# LEFT_CCM.net
KiCad netlist of a schematic drawn in Altium Designer
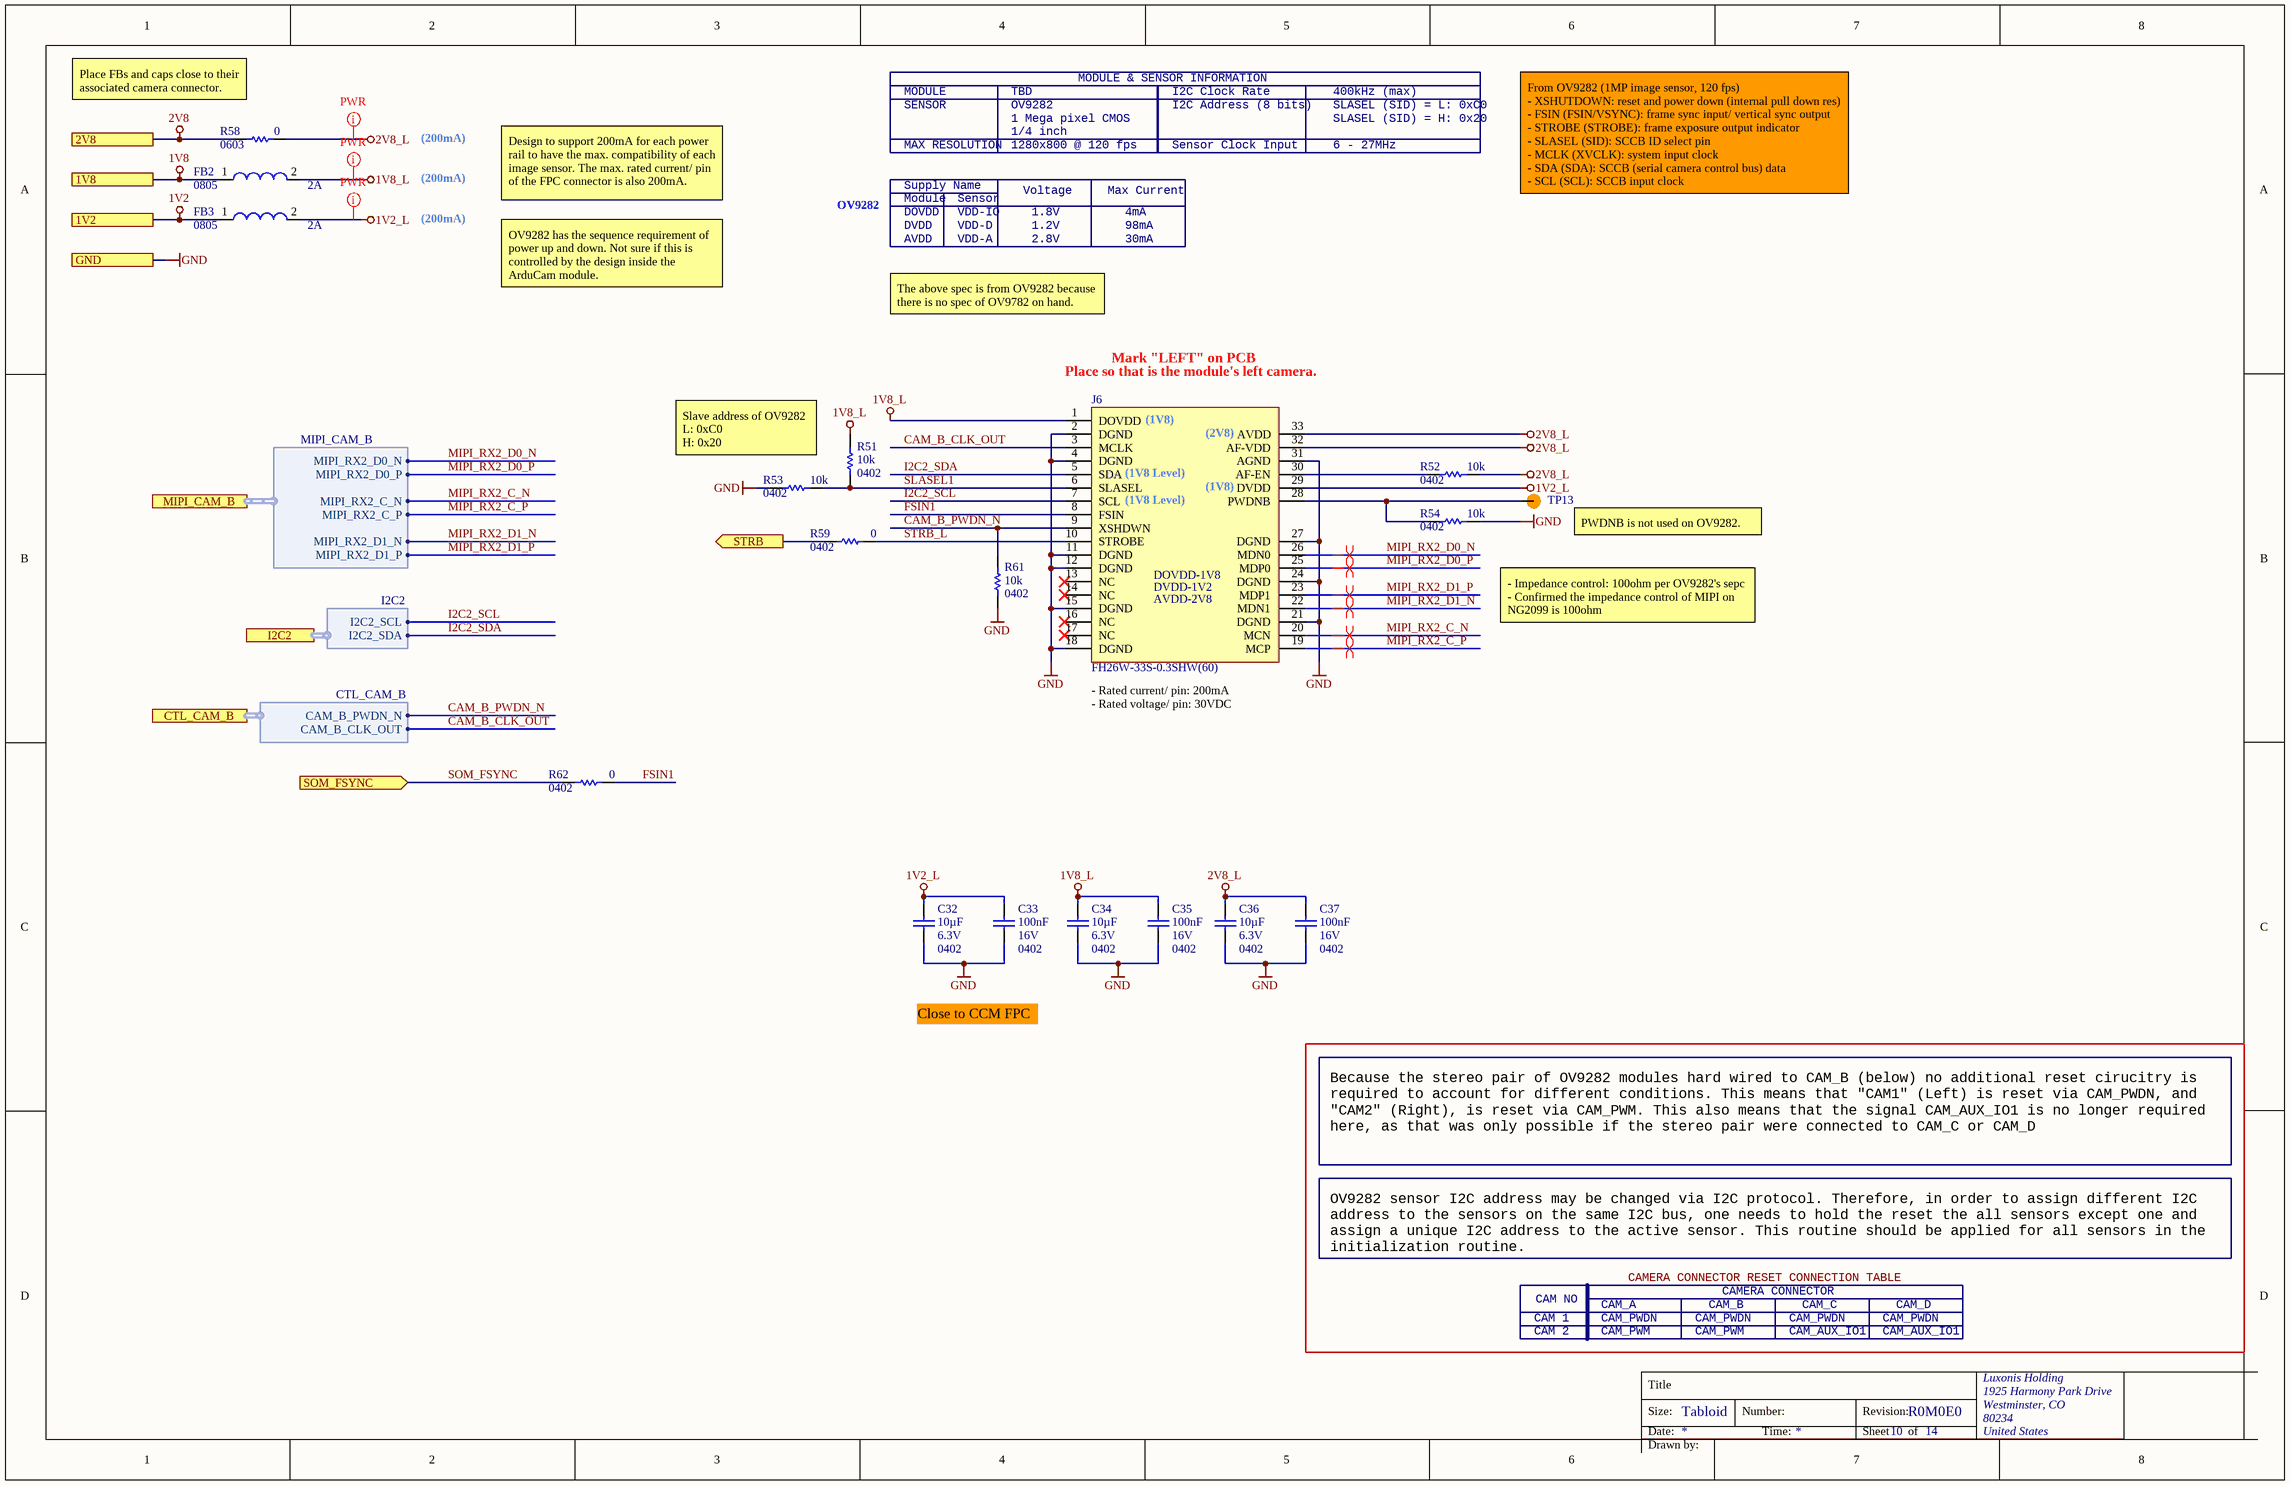
[diagram p0: LEFT_CCM.SchDoc]

(export (version "E")
  (design (tool "Eeschema 10.0.6"))
  (components
    (comp (ref "C32")
      (value "10µF")
      (footprint "CAPC0402(1005)70_N")
      (description "CAP CER 10UF 6.3V X5R 0402 20%")
      (fields
        (field (name "VOLTAGE RATING") "6.3V")
        (field (name "CASE/PACKAGE") "0402")
        (field (name "TOLERANCE") "20%")
        (field (name "Comment") "GRM155R60J106ME15D")
      )
      (libsource (lib "Luxonis LLC") (part "LLL153C70G474ME17E"))
    )
    (comp (ref "C33")
      (value "100nF")
      (footprint "CAPC0402(1005)60_N")
      (description "CAP CER 0.1UF 16V X7R 0402 10%")
      (fields
        (field (name "VOLTAGE RATING") "16V")
        (field (name "CASE/PACKAGE") "0402")
        (field (name "TOLERANCE") "10%")
        (field (name "Comment") "CL05B104KO5NFNC")
      )
      (libsource (lib "Luxonis LLC") (part "GRM188R61C475KAAJD"))
    )
    (comp (ref "C34")
      (value "10µF")
      (footprint "CAPC0402(1005)70_N")
      (description "CAP CER 10UF 6.3V X5R 0402 20%")
      (fields
        (field (name "VOLTAGE RATING") "6.3V")
        (field (name "CASE/PACKAGE") "0402")
        (field (name "TOLERANCE") "20%")
        (field (name "Comment") "GRM155R60J106ME15D")
      )
      (libsource (lib "Luxonis LLC") (part "LLL153C70G474ME17E"))
    )
    (comp (ref "C35")
      (value "100nF")
      (footprint "CAPC0402(1005)60_N")
      (description "CAP CER 0.1UF 16V X7R 0402 10%")
      (fields
        (field (name "VOLTAGE RATING") "16V")
        (field (name "CASE/PACKAGE") "0402")
        (field (name "TOLERANCE") "10%")
        (field (name "Comment") "CL05B104KO5NFNC")
      )
      (libsource (lib "Luxonis LLC") (part "GRM188R61C475KAAJD"))
    )
    (comp (ref "C36")
      (value "10µF")
      (footprint "CAPC0402(1005)70_N")
      (description "CAP CER 10UF 6.3V X5R 0402 20%")
      (fields
        (field (name "VOLTAGE RATING") "6.3V")
        (field (name "CASE/PACKAGE") "0402")
        (field (name "TOLERANCE") "20%")
        (field (name "Comment") "GRM155R60J106ME15D")
      )
      (libsource (lib "Luxonis LLC") (part "LLL153C70G474ME17E"))
    )
    (comp (ref "C37")
      (value "100nF")
      (footprint "CAPC0402(1005)60_N")
      (description "CAP CER 0.1UF 16V X7R 0402 10%")
      (fields
        (field (name "VOLTAGE RATING") "16V")
        (field (name "CASE/PACKAGE") "0402")
        (field (name "TOLERANCE") "10%")
        (field (name "Comment") "CL05B104KO5NFNC")
      )
      (libsource (lib "Luxonis LLC") (part "GRM188R61C475KAAJD"))
    )
    (comp (ref "FB2")
      (value "2508056017Y2")
      (footprint "2508056017Y2")
      (description "FERRITE BEAD, 0.1OHM, 2A, 0805, 600R/100MHz")
      (fields
        (field (name "CURRENT RATING") "2A")
        (field (name "CASE/PACKAGE") "0805")
        (field (name "TOLERANCE") "25%")
      )
      (libsource (lib "Luxonis LLC") (part "2508056017Y2"))
    )
    (comp (ref "FB3")
      (value "2508056017Y2")
      (footprint "2508056017Y2")
      (description "FERRITE BEAD, 0.1OHM, 2A, 0805, 600R/100MHz")
      (fields
        (field (name "CURRENT RATING") "2A")
        (field (name "CASE/PACKAGE") "0805")
        (field (name "TOLERANCE") "25%")
      )
      (libsource (lib "Luxonis LLC") (part "2508056017Y2"))
    )
    (comp (ref "J6")
      (value "FH26W-33S-0.3SHW(60)")
      (footprint "AC-PY003-OV9282")
      (description "FFC/FPC Connector, 33 Contact(s), 1 Row(s), Female, Right Angle, Surface Mount Terminal")
      (libsource (lib "LuxonisMaster") (part "AC_PY003-OV9282_CON"))
    )
    (comp (ref "R51")
      (value "10k")
      (footprint "RESC0402(1005)_N")
      (description "RES SMD 10K OHM 1% 1/16W 0402")
      (fields
        (field (name "CASE/PACKAGE") "0402")
        (field (name "TOLERANCE") "1%")
        (field (name "Comment") "RC0402FR-1310KL")
      )
      (libsource (lib "Luxonis LLC") (part "RC0402FR-0722RL_1"))
    )
    (comp (ref "R52")
      (value "10k")
      (footprint "RESC0402(1005)_N")
      (description "RES SMD 10K OHM 1% 1/16W 0402")
      (fields
        (field (name "CASE/PACKAGE") "0402")
        (field (name "TOLERANCE") "1%")
        (field (name "Comment") "RC0402FR-1310KL")
      )
      (libsource (lib "Luxonis LLC") (part "RC0402FR-0722RL_1"))
    )
    (comp (ref "R53")
      (value "10k")
      (footprint "RESC0402(1005)_N")
      (description "RES SMD 10K OHM 1% 1/16W 0402")
      (fields
        (field (name "CASE/PACKAGE") "0402")
        (field (name "TOLERANCE") "1%")
        (field (name "Comment") "RC0402FR-1310KL")
      )
      (libsource (lib "Luxonis LLC") (part "RC0402FR-0722RL_1"))
    )
    (comp (ref "R54")
      (value "10k")
      (footprint "RESC0402(1005)_N")
      (description "RES SMD 10K OHM 1% 1/16W 0402")
      (fields
        (field (name "CASE/PACKAGE") "0402")
        (field (name "TOLERANCE") "1%")
        (field (name "Comment") "RC0402FR-1310KL")
      )
      (libsource (lib "Luxonis LLC") (part "RC0402FR-0722RL_1"))
    )
    (comp (ref "R58")
      (value "0")
      (footprint "RESC0603(1608)_N")
      (description "RES SMD 0 OHM 5% 1/10W 0603")
      (fields
        (field (name "TOLERANCE") "5%")
        (field (name "CASE/PACKAGE") "0603")
        (field (name "Comment") "CRCW06030000Z0EA")
      )
      (libsource (lib "Luxonis LLC") (part "RC0402FR-0722RL_1"))
    )
    (comp (ref "R59")
      (value "0")
      (footprint "RESC0402(1005)_L")
      (description "RES SMD 0 OHM 5% 1/16W 0402")
      (fields
        (field (name "CASE/PACKAGE") "0402")
        (field (name "TOLERANCE") "5%")
        (field (name "Comment") "CRCW04020000Z0ED")
      )
      (libsource (lib "Luxonis LLC") (part "Default resistor symbol"))
    )
    (comp (ref "R61")
      (value "10k")
      (footprint "RESC0402(1005)_N")
      (description "RES SMD 10K OHM 1% 1/16W 0402")
      (fields
        (field (name "CASE/PACKAGE") "0402")
        (field (name "TOLERANCE") "1%")
        (field (name "Comment") "RC0402FR-1310KL")
      )
      (libsource (lib "Luxonis LLC") (part "RC0402FR-0722RL_1"))
    )
    (comp (ref "R62")
      (value "0")
      (footprint "RESC0402(1005)_L")
      (description "RES SMD 0 OHM 5% 1/16W 0402")
      (fields
        (field (name "CASE/PACKAGE") "0402")
        (field (name "TOLERANCE") "5%")
        (field (name "Comment") "CRCW04020000Z0ED")
      )
      (libsource (lib "Luxonis LLC") (part "Default resistor symbol"))
    )
    (comp (ref "TP13")
      (value "TP075_150_NS")
      (footprint "LuxonisMaster:TP075_150_NS")
      (libsource (lib "LuxonisMaster") (part "TEST_POINT"))
    )
  )
  (nets
    (net (code "4") (name "/CAM_B_CLK_OUT") (class "Default")
      (node (ref "J6") (pin "3") (pinfunction "MCLK_3") (pintype "passive"))
    )
    (net (code "5") (name "/CAM_B_PWDN_N") (class "Default")
      (node (ref "J6") (pin "9") (pinfunction "XSHDWN_9") (pintype "passive"))
      (node (ref "R61") (pin "2") (pinfunction "2_2") (pintype "passive"))
    )
    (net (code "6") (name "/FSIN1") (class "Default")
      (node (ref "J6") (pin "8") (pinfunction "FSIN_8") (pintype "passive"))
      (node (ref "R62") (pin "1") (pinfunction "1_1") (pintype "passive"))
    )
    (net (code "7") (name "/I2C2_SCL") (class "Default")
      (node (ref "J6") (pin "7") (pinfunction "SCL_7") (pintype "passive"))
    )
    (net (code "8") (name "/I2C2_SDA") (class "Default")
      (node (ref "J6") (pin "5") (pinfunction "SDA_5") (pintype "passive"))
    )
    (net (code "9") (name "/MIPI_RX2_C_N") (class "Default")
      (node (ref "J6") (pin "20") (pinfunction "MCN_20") (pintype "passive"))
    )
    (net (code "10") (name "/MIPI_RX2_C_P") (class "Default")
      (node (ref "J6") (pin "19") (pinfunction "MCP_19") (pintype "passive"))
    )
    (net (code "11") (name "/MIPI_RX2_D0_N") (class "Default")
      (node (ref "J6") (pin "26") (pinfunction "MDN0_26") (pintype "passive"))
    )
    (net (code "12") (name "/MIPI_RX2_D0_P") (class "Default")
      (node (ref "J6") (pin "25") (pinfunction "MDP0_25") (pintype "passive"))
    )
    (net (code "13") (name "/MIPI_RX2_D1_N") (class "Default")
      (node (ref "J6") (pin "22") (pinfunction "MDN1_22") (pintype "passive"))
    )
    (net (code "14") (name "/MIPI_RX2_D1_P") (class "Default")
      (node (ref "J6") (pin "23") (pinfunction "MDP1_23") (pintype "passive"))
    )
    (net (code "15") (name "/SLASEL1") (class "Default")
      (node (ref "J6") (pin "6") (pinfunction "SLASEL_6") (pintype "passive"))
      (node (ref "R51") (pin "1") (pinfunction "1_1") (pintype "passive"))
      (node (ref "R53") (pin "2") (pinfunction "2_2") (pintype "passive"))
    )
    (net (code "16") (name "/SOM_FSYNC") (class "Default")
      (node (ref "R62") (pin "2") (pinfunction "2_2") (pintype "passive"))
    )
    (net (code "17") (name "/STRB") (class "Default")
      (node (ref "R59") (pin "2") (pinfunction "2_2") (pintype "passive"))
    )
    (net (code "18") (name "/STRB_L") (class "Default")
      (node (ref "J6") (pin "10") (pinfunction "STROBE_10") (pintype "passive"))
      (node (ref "R59") (pin "1") (pinfunction "1_1") (pintype "passive"))
    )
    (net (code "22") (name "1V2") (class "Default")
      (node (ref "FB3") (pin "1") (pinfunction "1_1") (pintype "passive"))
    )
    (net (code "23") (name "1V2_L") (class "Default")
      (node (ref "C32") (pin "2") (pinfunction "2_2") (pintype "passive"))
      (node (ref "C33") (pin "2") (pinfunction "2_2") (pintype "passive"))
      (node (ref "FB3") (pin "2") (pinfunction "2_2") (pintype "passive"))
      (node (ref "J6") (pin "29") (pinfunction "DVDD_29") (pintype "passive"))
    )
    (net (code "24") (name "1V8") (class "Default")
      (node (ref "FB2") (pin "1") (pinfunction "1_1") (pintype "passive"))
    )
    (net (code "25") (name "1V8_L") (class "Default")
      (node (ref "C34") (pin "2") (pinfunction "2_2") (pintype "passive"))
      (node (ref "C35") (pin "2") (pinfunction "2_2") (pintype "passive"))
      (node (ref "FB2") (pin "2") (pinfunction "2_2") (pintype "passive"))
      (node (ref "J6") (pin "1") (pinfunction "DOVDD_1") (pintype "passive"))
      (node (ref "R51") (pin "2") (pinfunction "2_2") (pintype "passive"))
    )
    (net (code "26") (name "2V8") (class "Default")
      (node (ref "R58") (pin "1") (pinfunction "1_1") (pintype "passive"))
    )
    (net (code "27") (name "2V8_L") (class "Default")
      (node (ref "C36") (pin "2") (pinfunction "2_2") (pintype "passive"))
      (node (ref "C37") (pin "2") (pinfunction "2_2") (pintype "passive"))
      (node (ref "J6") (pin "32") (pinfunction "AF-VDD_32") (pintype "passive"))
      (node (ref "J6") (pin "33") (pinfunction "AVDD_33") (pintype "passive"))
      (node (ref "R52") (pin "2") (pinfunction "2_2") (pintype "passive"))
      (node (ref "R58") (pin "2") (pinfunction "2_2") (pintype "passive"))
    )
    (net (code "28") (name "GND") (class "Default")
      (node (ref "C32") (pin "1") (pinfunction "1_1") (pintype "passive"))
      (node (ref "C33") (pin "1") (pinfunction "1_1") (pintype "passive"))
      (node (ref "C34") (pin "1") (pinfunction "1_1") (pintype "passive"))
      (node (ref "C35") (pin "1") (pinfunction "1_1") (pintype "passive"))
      (node (ref "C36") (pin "1") (pinfunction "1_1") (pintype "passive"))
      (node (ref "C37") (pin "1") (pinfunction "1_1") (pintype "passive"))
      (node (ref "J6") (pin "11") (pinfunction "DGND_11") (pintype "passive"))
      (node (ref "J6") (pin "12") (pinfunction "DGND_12") (pintype "passive"))
      (node (ref "J6") (pin "15") (pinfunction "DGND_15") (pintype "passive"))
      (node (ref "J6") (pin "18") (pinfunction "DGND_18") (pintype "passive"))
      (node (ref "J6") (pin "2") (pinfunction "DGND_2") (pintype "passive"))
      (node (ref "J6") (pin "21") (pinfunction "DGND_21") (pintype "passive"))
      (node (ref "J6") (pin "24") (pinfunction "DGND_24") (pintype "passive"))
      (node (ref "J6") (pin "27") (pinfunction "DGND_27") (pintype "passive"))
      (node (ref "J6") (pin "31") (pinfunction "AGND_31") (pintype "passive"))
      (node (ref "J6") (pin "4") (pinfunction "DGND_4") (pintype "passive"))
      (node (ref "R53") (pin "1") (pinfunction "1_1") (pintype "passive"))
      (node (ref "R54") (pin "2") (pinfunction "2_2") (pintype "passive"))
      (node (ref "R61") (pin "1") (pinfunction "1_1") (pintype "passive"))
    )
    (net (code "29") (name "Net-(J6-AF-EN)") (class "Default")
      (node (ref "J6") (pin "30") (pinfunction "AF-EN_30") (pintype "passive"))
      (node (ref "R52") (pin "1") (pinfunction "1_1") (pintype "passive"))
    )
    (net (code "30") (name "Net-(J6-PWDNB)") (class "Default")
      (node (ref "J6") (pin "28") (pinfunction "PWDNB_28") (pintype "passive"))
      (node (ref "R54") (pin "1") (pinfunction "1_1") (pintype "passive"))
      (node (ref "TP13") (pin "1") (pintype "passive"))
    )
    (net (code "31") (name "unconnected-(J6-NC-Pad13)") (class "Default")
      (node (ref "J6") (pin "13") (pinfunction "NC_13") (pintype "passive+no_connect"))
    )
    (net (code "32") (name "unconnected-(J6-NC-Pad14)") (class "Default")
      (node (ref "J6") (pin "14") (pinfunction "NC_14") (pintype "passive+no_connect"))
    )
    (net (code "33") (name "unconnected-(J6-NC-Pad16)") (class "Default")
      (node (ref "J6") (pin "16") (pinfunction "NC_16") (pintype "passive+no_connect"))
    )
    (net (code "34") (name "unconnected-(J6-NC-Pad17)") (class "Default")
      (node (ref "J6") (pin "17") (pinfunction "NC_17") (pintype "passive+no_connect"))
    )
  )
)
